# SHDN-BSPD-S04-V00-BSPDDelay.net
KiCad netlist of a schematic drawn in Altium Designer
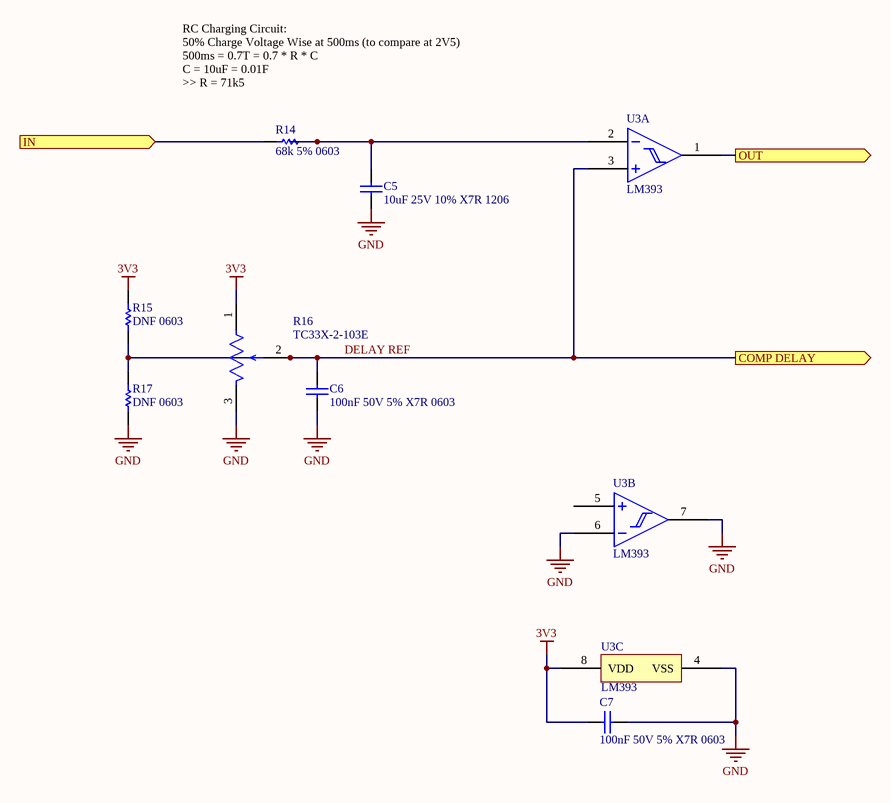
[diagram p0: SHDN-BSPD-S04-V00-BSPDDelay.SchDoc]

(export (version "E")
  (design (tool "Eeschema 10.0.6"))
  (components
    (comp (ref "C5")
      (value "10uF 25V 10% X7R 1206")
      (footprint "Cap_Ceramic_1206")
      (description "Capacitor, Ceramic, SMD, 10uF, 25V, 10%, X7R, 1206")
      (libsource (lib "StandardCapacitors") (part "10uF 25V 10% X7R 1206"))
    )
    (comp (ref "C6")
      (value "100nF 50V 5% X7R 0603")
      (footprint "Cap_Ceramic_0603")
      (description "Capacitor, Ceramic, SMD, 100nF, 50V, 5%, X7R, 0603")
      (libsource (lib "StandardCapacitors") (part "100nF 50V 5% X7R 0603"))
    )
    (comp (ref "C7")
      (value "100nF 50V 5% X7R 0603")
      (footprint "Cap_Ceramic_0603")
      (description "Capacitor, Ceramic, SMD, 100nF, 50V, 5%, X7R, 0603")
      (libsource (lib "StandardCapacitors") (part "100nF 50V 5% X7R 0603"))
    )
    (comp (ref "R14")
      (value "68k 5% 0603")
      (footprint "Res_ThinFilm_0603")
      (description "Resistor, SMD, 68k, 0.1W, 5%, 0603")
      (libsource (lib "StandardResistors") (part "68k 5% 0603"))
    )
    (comp (ref "R15")
      (value "DNF 0603")
      (footprint "Res_ThinFilm_0603")
      (description "Resistor, SMD, DNF, 0.1W, 0603")
      (libsource (lib "StandardResistors") (part "DNF 0603"))
    )
    (comp (ref "R16")
      (value "TC33X-2-103E")
      (footprint "TC33")
      (description "10 kOhms 0.1W, 1/10W J Lead Surface Mount Trimmer Potentiometer Cermet 1 Turn Top Adjustment")
      (libsource (lib "QUTMS_TrimmerLibrary") (part "TC33X-2-103E"))
    )
    (comp (ref "R17")
      (value "DNF 0603")
      (footprint "Res_ThinFilm_0603")
      (description "Resistor, SMD, DNF, 0.1W, 0603")
      (libsource (lib "StandardResistors") (part "DNF 0603"))
    )
    (comp (ref "U3")
      (value "LM393")
      (footprint "TSSOP-8")
      (description "General Purpose Comparitor 2 Circuit 8-SOIC")
      (libsource (lib "") (part "LM393_1"))
    )
  )
  (nets
    (net (code "1") (name "/DELAY REF") (class "Default")
      (node (ref "C6") (pin "2") (pinfunction "2_2") (pintype "passive"))
      (node (ref "R15") (pin "1") (pinfunction "1_1") (pintype "passive"))
      (node (ref "R16") (pin "2") (pinfunction "2_2") (pintype "passive"))
      (node (ref "R17") (pin "2") (pinfunction "2_2") (pintype "passive"))
      (node (ref "U3") (pin "3") (pinfunction "IN1+_3") (pintype "passive"))
    )
    (net (code "2") (name "/IN") (class "Default")
      (node (ref "R14") (pin "1") (pinfunction "1_1") (pintype "passive"))
    )
    (net (code "3") (name "/OUT") (class "Default")
      (node (ref "U3") (pin "1") (pinfunction "OUT1_1") (pintype "passive"))
    )
    (net (code "4") (name "3V3") (class "Default")
      (node (ref "C7") (pin "2") (pinfunction "2_2") (pintype "passive"))
      (node (ref "R15") (pin "2") (pinfunction "2_2") (pintype "passive"))
      (node (ref "R16") (pin "1") (pinfunction "1_1") (pintype "passive"))
      (node (ref "U3") (pin "8") (pinfunction "VDD_8") (pintype "passive"))
    )
    (net (code "5") (name "GND") (class "Default")
      (node (ref "C5") (pin "1") (pinfunction "1_1") (pintype "passive"))
      (node (ref "C6") (pin "1") (pinfunction "1_1") (pintype "passive"))
      (node (ref "C7") (pin "1") (pinfunction "1_1") (pintype "passive"))
      (node (ref "R16") (pin "3") (pinfunction "3_3") (pintype "passive"))
      (node (ref "R17") (pin "1") (pinfunction "1_1") (pintype "passive"))
      (node (ref "U3") (pin "4") (pinfunction "VSS_4") (pintype "passive"))
      (node (ref "U3") (pin "6") (pinfunction "IN2-_6") (pintype "passive"))
      (node (ref "U3") (pin "7") (pinfunction "OUT1_7") (pintype "passive"))
    )
    (net (code "6") (name "Net-(U3A-IN1-)") (class "Default")
      (node (ref "C5") (pin "2") (pinfunction "2_2") (pintype "passive"))
      (node (ref "R14") (pin "2") (pinfunction "2_2") (pintype "passive"))
      (node (ref "U3") (pin "2") (pinfunction "IN1-_2") (pintype "passive"))
    )
    (net (code "7") (name "unconnected-(U3B-IN2+-Pad5)") (class "Default")
      (node (ref "U3") (pin "5") (pinfunction "IN2+_5") (pintype "passive"))
    )
  )
)
